# LED_STATUS.net
KiCad netlist of a schematic drawn in Altium Designer
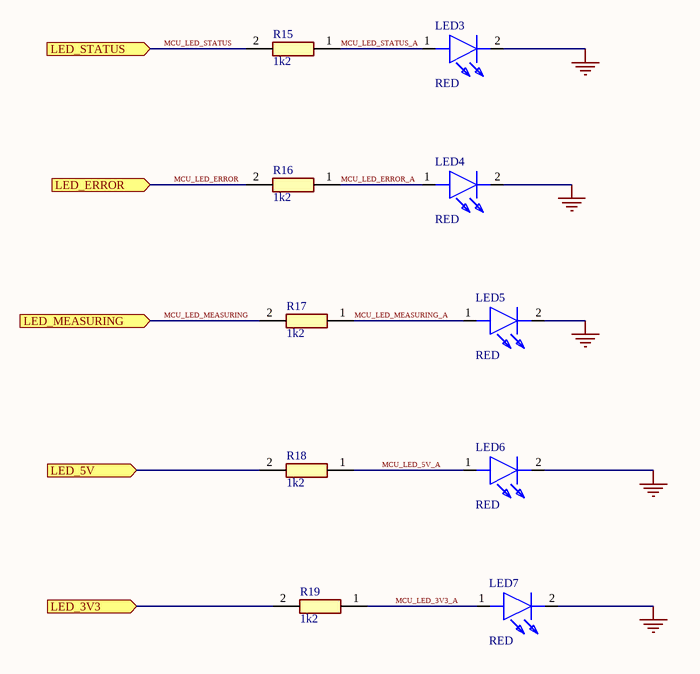
[diagram p0: LED_STATUS.SchDoc]

(export (version "E")
  (design (tool "Eeschema 10.0.6"))
  (components
    (comp (ref "LED3")
      (value "RED")
      (footprint "SamacSys:APT2012SECKJ3PRV")
      (description "LED")
      (fields
        (field (name "MANUFACTURER_PART_NUMBER") "APT2012SECK/J3-PRV")
        (field (name "MOUSER PART NUMBER") "604-APT2012SECKJ3PRV")
      )
      (libsource (lib "*") (part "APT2012SECK_J3-PRV"))
    )
    (comp (ref "LED4")
      (value "RED")
      (footprint "SamacSys:APT2012SECKJ3PRV")
      (description "LED")
      (fields
        (field (name "MANUFACTURER_PART_NUMBER") "APT2012SECK/J3-PRV")
        (field (name "MOUSER PART NUMBER") "604-APT2012SECKJ3PRV")
      )
      (libsource (lib "*") (part "APT2012SECK_J3-PRV"))
    )
    (comp (ref "LED5")
      (value "RED")
      (footprint "SamacSys:APT2012SECKJ3PRV")
      (description "LED")
      (fields
        (field (name "MANUFACTURER_PART_NUMBER") "APT2012SECK/J3-PRV")
        (field (name "MOUSER PART NUMBER") "604-APT2012SECKJ3PRV")
      )
      (libsource (lib "*") (part "APT2012SECK_J3-PRV"))
    )
    (comp (ref "LED6")
      (value "RED")
      (footprint "SamacSys:APT2012SECKJ3PRV")
      (description "LED")
      (fields
        (field (name "MANUFACTURER_PART_NUMBER") "APT2012SECK/J3-PRV")
        (field (name "MOUSER PART NUMBER") "604-APT2012SECKJ3PRV")
      )
      (libsource (lib "*") (part "APT2012SECK_J3-PRV"))
    )
    (comp (ref "LED7")
      (value "RED")
      (footprint "SamacSys:APT2012SECKJ3PRV")
      (description "LED")
      (fields
        (field (name "MANUFACTURER_PART_NUMBER") "APT2012SECK/J3-PRV")
        (field (name "MOUSER PART NUMBER") "604-APT2012SECKJ3PRV")
      )
      (libsource (lib "*") (part "APT2012SECK_J3-PRV"))
    )
    (comp (ref "R15")
      (value "1k2")
      (footprint "SamacSys:RESC1608X55N")
      (description "Resistor")
      (fields
        (field (name "MANUFACTURER_PART_NUMBER") "RK73B1JTTD103J")
        (field (name "MOUSER PART NUMBER") "660-RK73B1JTTD103J")
      )
      (libsource (lib "*") (part "RK73B1JTTD103J"))
    )
    (comp (ref "R16")
      (value "1k2")
      (footprint "SamacSys:RESC1608X55N")
      (description "Resistor")
      (fields
        (field (name "MANUFACTURER_PART_NUMBER") "RK73B1JTTD103J")
        (field (name "MOUSER PART NUMBER") "660-RK73B1JTTD103J")
      )
      (libsource (lib "*") (part "RK73B1JTTD103J"))
    )
    (comp (ref "R17")
      (value "1k2")
      (footprint "SamacSys:RESC1608X55N")
      (description "Resistor")
      (fields
        (field (name "MANUFACTURER_PART_NUMBER") "RK73B1JTTD103J")
        (field (name "MOUSER PART NUMBER") "660-RK73B1JTTD103J")
      )
      (libsource (lib "*") (part "RK73B1JTTD103J"))
    )
    (comp (ref "R18")
      (value "1k2")
      (footprint "SamacSys:RESC1608X55N")
      (description "Resistor")
      (fields
        (field (name "MANUFACTURER_PART_NUMBER") "RK73B1JTTD103J")
        (field (name "MOUSER PART NUMBER") "660-RK73B1JTTD103J")
      )
      (libsource (lib "*") (part "RK73B1JTTD103J"))
    )
    (comp (ref "R19")
      (value "1k2")
      (footprint "SamacSys:RESC1608X55N")
      (description "Resistor")
      (fields
        (field (name "MANUFACTURER_PART_NUMBER") "RK73B1JTTD103J")
        (field (name "MOUSER PART NUMBER") "660-RK73B1JTTD103J")
      )
      (libsource (lib "*") (part "RK73B1JTTD103J"))
    )
  )
  (nets
    (net (code "1") (name "/LED_3V3") (class "Default")
      (node (ref "R19") (pin "2") (pinfunction "2_2") (pintype "passive"))
    )
    (net (code "2") (name "/LED_5V") (class "Default")
      (node (ref "R18") (pin "2") (pinfunction "2_2") (pintype "passive"))
    )
    (net (code "3") (name "/MCU_LED_3V3_A") (class "Default")
      (node (ref "LED7") (pin "1") (pinfunction "A_1") (pintype "passive"))
      (node (ref "R19") (pin "1") (pinfunction "1_1") (pintype "passive"))
    )
    (net (code "4") (name "/MCU_LED_5V_A") (class "Default")
      (node (ref "LED6") (pin "1") (pinfunction "A_1") (pintype "passive"))
      (node (ref "R18") (pin "1") (pinfunction "1_1") (pintype "passive"))
    )
    (net (code "5") (name "/MCU_LED_ERROR") (class "Default")
      (node (ref "R16") (pin "2") (pinfunction "2_2") (pintype "passive"))
    )
    (net (code "6") (name "/MCU_LED_ERROR_A") (class "Default")
      (node (ref "LED4") (pin "1") (pinfunction "A_1") (pintype "passive"))
      (node (ref "R16") (pin "1") (pinfunction "1_1") (pintype "passive"))
    )
    (net (code "7") (name "/MCU_LED_MEASURING") (class "Default")
      (node (ref "R17") (pin "2") (pinfunction "2_2") (pintype "passive"))
    )
    (net (code "8") (name "/MCU_LED_MEASURING_A") (class "Default")
      (node (ref "LED5") (pin "1") (pinfunction "A_1") (pintype "passive"))
      (node (ref "R17") (pin "1") (pinfunction "1_1") (pintype "passive"))
    )
    (net (code "9") (name "/MCU_LED_STATUS") (class "Default")
      (node (ref "R15") (pin "2") (pinfunction "2_2") (pintype "passive"))
    )
    (net (code "10") (name "/MCU_LED_STATUS_A") (class "Default")
      (node (ref "LED3") (pin "1") (pinfunction "A_1") (pintype "passive"))
      (node (ref "R15") (pin "1") (pinfunction "1_1") (pintype "passive"))
    )
    (net (code "11") (name "GND") (class "Default")
      (node (ref "LED3") (pin "2") (pinfunction "K_2") (pintype "passive"))
      (node (ref "LED4") (pin "2") (pinfunction "K_2") (pintype "passive"))
      (node (ref "LED5") (pin "2") (pinfunction "K_2") (pintype "passive"))
      (node (ref "LED6") (pin "2") (pinfunction "K_2") (pintype "passive"))
      (node (ref "LED7") (pin "2") (pinfunction "K_2") (pintype "passive"))
    )
  )
)
